# Breakout_Boosterpack.net
KiCad netlist of a schematic drawn in EAGLE
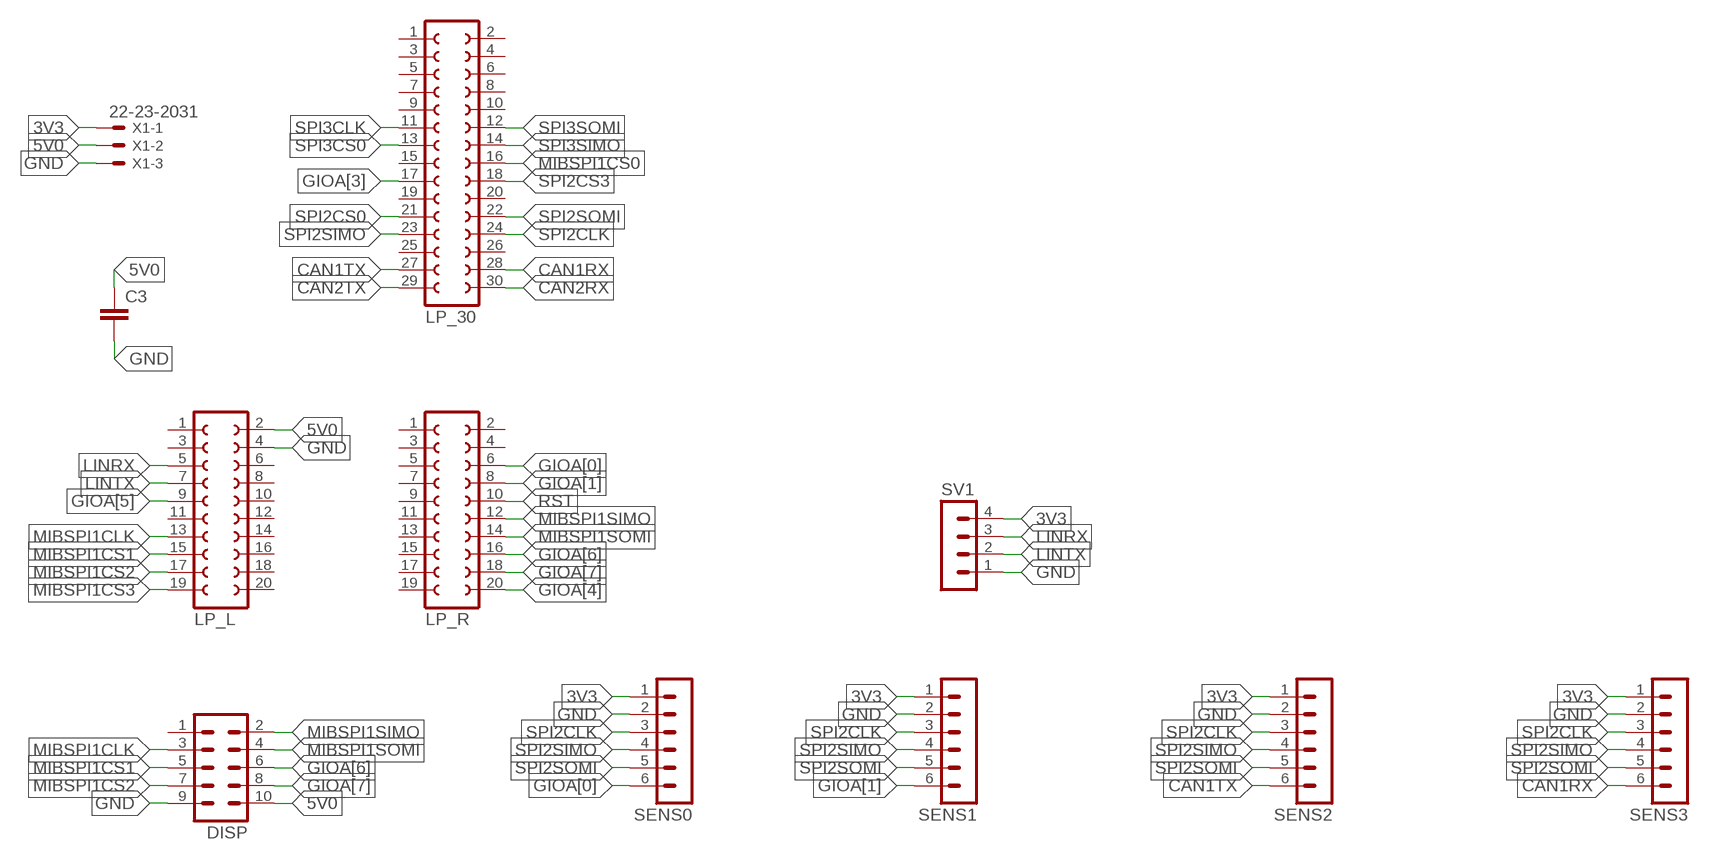
[diagram p0: schematic, sheet 1]

(export (version "E")
  (design (tool "Eeschema 10.0.6"))
  (components
    (comp (ref "C3")
      (value "C2.5/5")
      (footprint "eagle-import:C2.5-5")
      (libsource (lib "eagle-import") (part "C2.5/5"))
    )
    (comp (ref "DISP")
      (value "MA05-2")
      (footprint "eagle-import:MA05-2")
      (libsource (lib "eagle-import") (part "MA05-2"))
    )
    (comp (ref "LP_30")
      (value "FE15-2")
      (footprint "eagle-import:FE15-2")
      (libsource (lib "eagle-import") (part "FE15-2"))
    )
    (comp (ref "LP_L")
      (value "FE10-2")
      (footprint "eagle-import:FE10-2")
      (libsource (lib "eagle-import") (part "FE10-2"))
    )
    (comp (ref "LP_R")
      (value "FE10-2")
      (footprint "eagle-import:FE10-2")
      (libsource (lib "eagle-import") (part "FE10-2"))
    )
    (comp (ref "SENS0")
      (value "MA06-1")
      (footprint "eagle-import:MA06-1")
      (libsource (lib "eagle-import") (part "MA06-1"))
    )
    (comp (ref "SENS1")
      (value "MA06-1")
      (footprint "eagle-import:MA06-1")
      (libsource (lib "eagle-import") (part "MA06-1"))
    )
    (comp (ref "SENS2")
      (value "MA06-1")
      (footprint "eagle-import:MA06-1")
      (libsource (lib "eagle-import") (part "MA06-1"))
    )
    (comp (ref "SENS3")
      (value "MA06-1")
      (footprint "eagle-import:MA06-1")
      (libsource (lib "eagle-import") (part "MA06-1"))
    )
    (comp (ref "SV1")
      (value "MA04-1")
      (footprint "eagle-import:MA04-1")
      (libsource (lib "eagle-import") (part "MA04-1"))
    )
    (comp (ref "X1")
      (value "22-23-2031")
      (footprint "eagle-import:22-23-2031")
      (fields (field (name "MF") "MOLEX"))
      (libsource (lib "eagle-import") (part "22-23-2031"))
    )
  )
  (nets
    (net (code "1") (name "3V3") (class "Default")
      (node (ref "SENS0") (pin "1") (pinfunction "1_1") (pintype "passive"))
      (node (ref "SENS1") (pin "1") (pinfunction "1_1") (pintype "passive"))
      (node (ref "SENS2") (pin "1") (pinfunction "1_1") (pintype "passive"))
      (node (ref "SENS3") (pin "1") (pinfunction "1_1") (pintype "passive"))
      (node (ref "SV1") (pin "4") (pinfunction "4_4") (pintype "passive"))
      (node (ref "X1") (pin "1") (pinfunction "S_1") (pintype "passive"))
    )
    (net (code "2") (name "5V0") (class "Default")
      (node (ref "C3") (pin "1") (pinfunction "1_1") (pintype "passive"))
      (node (ref "DISP") (pin "10") (pinfunction "10_10") (pintype "passive"))
      (node (ref "LP_L") (pin "2") (pinfunction "2_2") (pintype "passive"))
      (node (ref "X1") (pin "2") (pinfunction "S_2") (pintype "passive"))
    )
    (net (code "3") (name "CAN1RX") (class "Default")
      (node (ref "LP_30") (pin "28") (pinfunction "28_28") (pintype "passive"))
      (node (ref "SENS3") (pin "6") (pinfunction "6_6") (pintype "passive"))
    )
    (net (code "4") (name "CAN1TX") (class "Default")
      (node (ref "LP_30") (pin "27") (pinfunction "27_27") (pintype "passive"))
      (node (ref "SENS2") (pin "6") (pinfunction "6_6") (pintype "passive"))
    )
    (net (code "5") (name "CAN2RX") (class "Default")
      (node (ref "LP_30") (pin "30") (pinfunction "30_30") (pintype "passive"))
    )
    (net (code "6") (name "CAN2TX") (class "Default")
      (node (ref "LP_30") (pin "29") (pinfunction "29_29") (pintype "passive"))
    )
    (net (code "7") (name "GIOA[0]") (class "Default")
      (node (ref "LP_R") (pin "6") (pinfunction "6_6") (pintype "passive"))
      (node (ref "SENS0") (pin "6") (pinfunction "6_6") (pintype "passive"))
    )
    (net (code "8") (name "GIOA[1]") (class "Default")
      (node (ref "LP_R") (pin "8") (pinfunction "8_8") (pintype "passive"))
      (node (ref "SENS1") (pin "6") (pinfunction "6_6") (pintype "passive"))
    )
    (net (code "9") (name "GIOA[3]") (class "Default")
      (node (ref "LP_30") (pin "17") (pinfunction "17_17") (pintype "passive"))
    )
    (net (code "10") (name "GIOA[4]") (class "Default")
      (node (ref "LP_R") (pin "20") (pinfunction "20_20") (pintype "passive"))
    )
    (net (code "11") (name "GIOA[5]") (class "Default")
      (node (ref "LP_L") (pin "9") (pinfunction "9_9") (pintype "passive"))
    )
    (net (code "12") (name "GIOA[6]") (class "Default")
      (node (ref "DISP") (pin "6") (pinfunction "6_6") (pintype "passive"))
      (node (ref "LP_R") (pin "16") (pinfunction "16_16") (pintype "passive"))
    )
    (net (code "13") (name "GIOA[7]") (class "Default")
      (node (ref "DISP") (pin "8") (pinfunction "8_8") (pintype "passive"))
      (node (ref "LP_R") (pin "18") (pinfunction "18_18") (pintype "passive"))
    )
    (net (code "14") (name "GND") (class "Default")
      (node (ref "C3") (pin "2") (pinfunction "2_2") (pintype "passive"))
      (node (ref "DISP") (pin "9") (pinfunction "9_9") (pintype "passive"))
      (node (ref "LP_L") (pin "4") (pinfunction "4_4") (pintype "passive"))
      (node (ref "SENS0") (pin "2") (pinfunction "2_2") (pintype "passive"))
      (node (ref "SENS1") (pin "2") (pinfunction "2_2") (pintype "passive"))
      (node (ref "SENS2") (pin "2") (pinfunction "2_2") (pintype "passive"))
      (node (ref "SENS3") (pin "2") (pinfunction "2_2") (pintype "passive"))
      (node (ref "SV1") (pin "1") (pinfunction "1_1") (pintype "passive"))
      (node (ref "X1") (pin "3") (pinfunction "S_3") (pintype "passive"))
    )
    (net (code "15") (name "LINRX") (class "Default")
      (node (ref "LP_L") (pin "5") (pinfunction "5_5") (pintype "passive"))
      (node (ref "SV1") (pin "3") (pinfunction "3_3") (pintype "passive"))
    )
    (net (code "16") (name "LINTX") (class "Default")
      (node (ref "LP_L") (pin "7") (pinfunction "7_7") (pintype "passive"))
      (node (ref "SV1") (pin "2") (pinfunction "2_2") (pintype "passive"))
    )
    (net (code "17") (name "MIBSPI1CLK") (class "Default")
      (node (ref "DISP") (pin "3") (pinfunction "3_3") (pintype "passive"))
      (node (ref "LP_L") (pin "13") (pinfunction "13_13") (pintype "passive"))
    )
    (net (code "18") (name "MIBSPI1CS0") (class "Default")
      (node (ref "LP_30") (pin "16") (pinfunction "16_16") (pintype "passive"))
    )
    (net (code "19") (name "MIBSPI1CS1") (class "Default")
      (node (ref "DISP") (pin "5") (pinfunction "5_5") (pintype "passive"))
      (node (ref "LP_L") (pin "15") (pinfunction "15_15") (pintype "passive"))
    )
    (net (code "20") (name "MIBSPI1CS2") (class "Default")
      (node (ref "DISP") (pin "7") (pinfunction "7_7") (pintype "passive"))
      (node (ref "LP_L") (pin "17") (pinfunction "17_17") (pintype "passive"))
    )
    (net (code "21") (name "MIBSPI1CS3") (class "Default")
      (node (ref "LP_L") (pin "19") (pinfunction "19_19") (pintype "passive"))
    )
    (net (code "22") (name "MIBSPI1SIMO") (class "Default")
      (node (ref "DISP") (pin "2") (pinfunction "2_2") (pintype "passive"))
      (node (ref "LP_R") (pin "12") (pinfunction "12_12") (pintype "passive"))
    )
    (net (code "23") (name "MIBSPI1SOMI") (class "Default")
      (node (ref "DISP") (pin "4") (pinfunction "4_4") (pintype "passive"))
      (node (ref "LP_R") (pin "14") (pinfunction "14_14") (pintype "passive"))
    )
    (net (code "24") (name "RST") (class "Default")
      (node (ref "LP_R") (pin "10") (pinfunction "10_10") (pintype "passive"))
    )
    (net (code "25") (name "SPI2CLK") (class "Default")
      (node (ref "LP_30") (pin "24") (pinfunction "24_24") (pintype "passive"))
      (node (ref "SENS0") (pin "3") (pinfunction "3_3") (pintype "passive"))
      (node (ref "SENS1") (pin "3") (pinfunction "3_3") (pintype "passive"))
      (node (ref "SENS2") (pin "3") (pinfunction "3_3") (pintype "passive"))
      (node (ref "SENS3") (pin "3") (pinfunction "3_3") (pintype "passive"))
    )
    (net (code "26") (name "SPI2CS0") (class "Default")
      (node (ref "LP_30") (pin "21") (pinfunction "21_21") (pintype "passive"))
    )
    (net (code "27") (name "SPI2CS3") (class "Default")
      (node (ref "LP_30") (pin "18") (pinfunction "18_18") (pintype "passive"))
    )
    (net (code "28") (name "SPI2SIMO") (class "Default")
      (node (ref "LP_30") (pin "23") (pinfunction "23_23") (pintype "passive"))
      (node (ref "SENS0") (pin "4") (pinfunction "4_4") (pintype "passive"))
      (node (ref "SENS1") (pin "4") (pinfunction "4_4") (pintype "passive"))
      (node (ref "SENS2") (pin "4") (pinfunction "4_4") (pintype "passive"))
      (node (ref "SENS3") (pin "4") (pinfunction "4_4") (pintype "passive"))
    )
    (net (code "29") (name "SPI2SOMI") (class "Default")
      (node (ref "LP_30") (pin "22") (pinfunction "22_22") (pintype "passive"))
      (node (ref "SENS0") (pin "5") (pinfunction "5_5") (pintype "passive"))
      (node (ref "SENS1") (pin "5") (pinfunction "5_5") (pintype "passive"))
      (node (ref "SENS2") (pin "5") (pinfunction "5_5") (pintype "passive"))
      (node (ref "SENS3") (pin "5") (pinfunction "5_5") (pintype "passive"))
    )
    (net (code "30") (name "SPI3CLK") (class "Default")
      (node (ref "LP_30") (pin "11") (pinfunction "11_11") (pintype "passive"))
    )
    (net (code "31") (name "SPI3CS0") (class "Default")
      (node (ref "LP_30") (pin "13") (pinfunction "13_13") (pintype "passive"))
    )
    (net (code "32") (name "SPI3SIMO") (class "Default")
      (node (ref "LP_30") (pin "14") (pinfunction "14_14") (pintype "passive"))
    )
    (net (code "33") (name "SPI3SOMI") (class "Default")
      (node (ref "LP_30") (pin "12") (pinfunction "12_12") (pintype "passive"))
    )
    (net (code "34") (name "unconnected-(DISP-Pad1)") (class "Default")
      (node (ref "DISP") (pin "1") (pinfunction "1_1") (pintype "passive"))
    )
    (net (code "35") (name "unconnected-(LP_30-Pad1)") (class "Default")
      (node (ref "LP_30") (pin "1") (pinfunction "1_1") (pintype "passive"))
    )
    (net (code "36") (name "unconnected-(LP_30-Pad2)") (class "Default")
      (node (ref "LP_30") (pin "2") (pinfunction "2_2") (pintype "passive"))
    )
    (net (code "37") (name "unconnected-(LP_30-Pad3)") (class "Default")
      (node (ref "LP_30") (pin "3") (pinfunction "3_3") (pintype "passive"))
    )
    (net (code "38") (name "unconnected-(LP_30-Pad4)") (class "Default")
      (node (ref "LP_30") (pin "4") (pinfunction "4_4") (pintype "passive"))
    )
    (net (code "39") (name "unconnected-(LP_30-Pad5)") (class "Default")
      (node (ref "LP_30") (pin "5") (pinfunction "5_5") (pintype "passive"))
    )
    (net (code "40") (name "unconnected-(LP_30-Pad6)") (class "Default")
      (node (ref "LP_30") (pin "6") (pinfunction "6_6") (pintype "passive"))
    )
    (net (code "41") (name "unconnected-(LP_30-Pad7)") (class "Default")
      (node (ref "LP_30") (pin "7") (pinfunction "7_7") (pintype "passive"))
    )
    (net (code "42") (name "unconnected-(LP_30-Pad8)") (class "Default")
      (node (ref "LP_30") (pin "8") (pinfunction "8_8") (pintype "passive"))
    )
    (net (code "43") (name "unconnected-(LP_30-Pad9)") (class "Default")
      (node (ref "LP_30") (pin "9") (pinfunction "9_9") (pintype "passive"))
    )
    (net (code "44") (name "unconnected-(LP_30-Pad10)") (class "Default")
      (node (ref "LP_30") (pin "10") (pinfunction "10_10") (pintype "passive"))
    )
    (net (code "45") (name "unconnected-(LP_30-Pad15)") (class "Default")
      (node (ref "LP_30") (pin "15") (pinfunction "15_15") (pintype "passive"))
    )
    (net (code "46") (name "unconnected-(LP_30-Pad19)") (class "Default")
      (node (ref "LP_30") (pin "19") (pinfunction "19_19") (pintype "passive"))
    )
    (net (code "47") (name "unconnected-(LP_30-Pad20)") (class "Default")
      (node (ref "LP_30") (pin "20") (pinfunction "20_20") (pintype "passive"))
    )
    (net (code "48") (name "unconnected-(LP_30-Pad25)") (class "Default")
      (node (ref "LP_30") (pin "25") (pinfunction "25_25") (pintype "passive"))
    )
    (net (code "49") (name "unconnected-(LP_30-Pad26)") (class "Default")
      (node (ref "LP_30") (pin "26") (pinfunction "26_26") (pintype "passive"))
    )
    (net (code "50") (name "unconnected-(LP_L-Pad1)") (class "Default")
      (node (ref "LP_L") (pin "1") (pinfunction "1_1") (pintype "passive"))
    )
    (net (code "51") (name "unconnected-(LP_L-Pad3)") (class "Default")
      (node (ref "LP_L") (pin "3") (pinfunction "3_3") (pintype "passive"))
    )
    (net (code "52") (name "unconnected-(LP_L-Pad6)") (class "Default")
      (node (ref "LP_L") (pin "6") (pinfunction "6_6") (pintype "passive"))
    )
    (net (code "53") (name "unconnected-(LP_L-Pad8)") (class "Default")
      (node (ref "LP_L") (pin "8") (pinfunction "8_8") (pintype "passive"))
    )
    (net (code "54") (name "unconnected-(LP_L-Pad10)") (class "Default")
      (node (ref "LP_L") (pin "10") (pinfunction "10_10") (pintype "passive"))
    )
    (net (code "55") (name "unconnected-(LP_L-Pad11)") (class "Default")
      (node (ref "LP_L") (pin "11") (pinfunction "11_11") (pintype "passive"))
    )
    (net (code "56") (name "unconnected-(LP_L-Pad12)") (class "Default")
      (node (ref "LP_L") (pin "12") (pinfunction "12_12") (pintype "passive"))
    )
    (net (code "57") (name "unconnected-(LP_L-Pad14)") (class "Default")
      (node (ref "LP_L") (pin "14") (pinfunction "14_14") (pintype "passive"))
    )
    (net (code "58") (name "unconnected-(LP_L-Pad16)") (class "Default")
      (node (ref "LP_L") (pin "16") (pinfunction "16_16") (pintype "passive"))
    )
    (net (code "59") (name "unconnected-(LP_L-Pad18)") (class "Default")
      (node (ref "LP_L") (pin "18") (pinfunction "18_18") (pintype "passive"))
    )
    (net (code "60") (name "unconnected-(LP_L-Pad20)") (class "Default")
      (node (ref "LP_L") (pin "20") (pinfunction "20_20") (pintype "passive"))
    )
    (net (code "61") (name "unconnected-(LP_R-Pad1)") (class "Default")
      (node (ref "LP_R") (pin "1") (pinfunction "1_1") (pintype "passive"))
    )
    (net (code "62") (name "unconnected-(LP_R-Pad2)") (class "Default")
      (node (ref "LP_R") (pin "2") (pinfunction "2_2") (pintype "passive"))
    )
    (net (code "63") (name "unconnected-(LP_R-Pad3)") (class "Default")
      (node (ref "LP_R") (pin "3") (pinfunction "3_3") (pintype "passive"))
    )
    (net (code "64") (name "unconnected-(LP_R-Pad4)") (class "Default")
      (node (ref "LP_R") (pin "4") (pinfunction "4_4") (pintype "passive"))
    )
    (net (code "65") (name "unconnected-(LP_R-Pad5)") (class "Default")
      (node (ref "LP_R") (pin "5") (pinfunction "5_5") (pintype "passive"))
    )
    (net (code "66") (name "unconnected-(LP_R-Pad7)") (class "Default")
      (node (ref "LP_R") (pin "7") (pinfunction "7_7") (pintype "passive"))
    )
    (net (code "67") (name "unconnected-(LP_R-Pad9)") (class "Default")
      (node (ref "LP_R") (pin "9") (pinfunction "9_9") (pintype "passive"))
    )
    (net (code "68") (name "unconnected-(LP_R-Pad11)") (class "Default")
      (node (ref "LP_R") (pin "11") (pinfunction "11_11") (pintype "passive"))
    )
    (net (code "69") (name "unconnected-(LP_R-Pad13)") (class "Default")
      (node (ref "LP_R") (pin "13") (pinfunction "13_13") (pintype "passive"))
    )
    (net (code "70") (name "unconnected-(LP_R-Pad15)") (class "Default")
      (node (ref "LP_R") (pin "15") (pinfunction "15_15") (pintype "passive"))
    )
    (net (code "71") (name "unconnected-(LP_R-Pad17)") (class "Default")
      (node (ref "LP_R") (pin "17") (pinfunction "17_17") (pintype "passive"))
    )
    (net (code "72") (name "unconnected-(LP_R-Pad19)") (class "Default")
      (node (ref "LP_R") (pin "19") (pinfunction "19_19") (pintype "passive"))
    )
  )
)
